# MCU_Board.net
KiCad netlist of a schematic drawn in Altium Designer
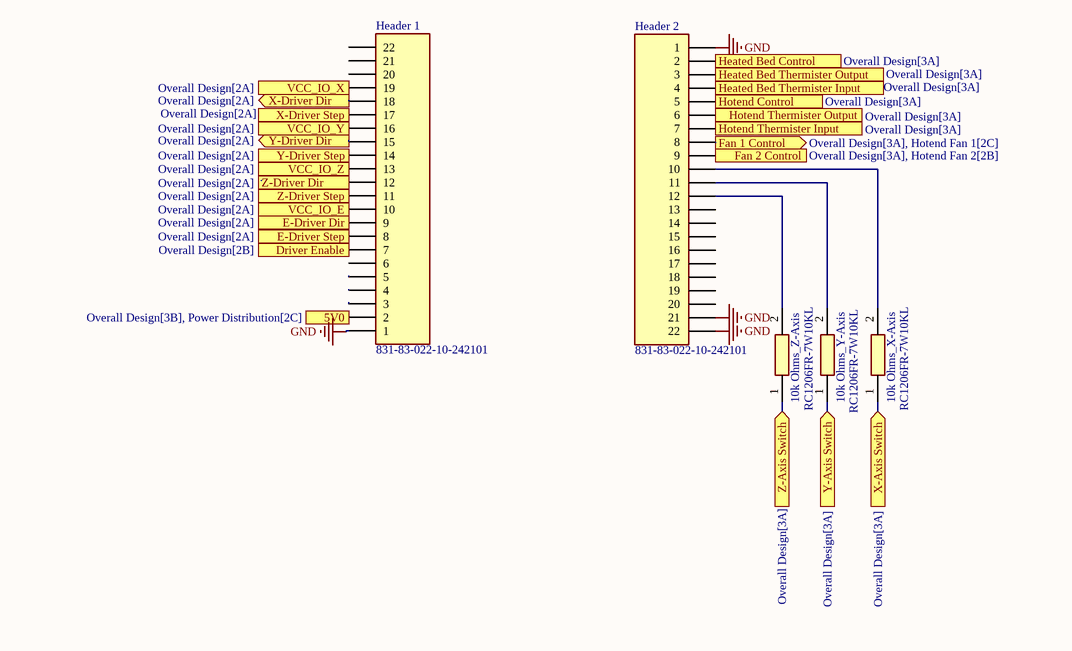
[diagram p0: MCU Board.SchDoc]

(export (version "E")
  (design (tool "Eeschema 10.0.6"))
  (components
    (comp (ref "10k Ohms_X-Axis")
      (value "RC1206FR-7W10KL")
      (footprint "SamacSys:RESC3116X65N")
      (description "Resistor")
      (libsource (lib "*") (part "RC1206FR-7W10KL"))
    )
    (comp (ref "10k Ohms_Y-Axis")
      (value "RC1206FR-7W10KL")
      (footprint "SamacSys:RESC3116X65N")
      (description "Resistor")
      (libsource (lib "*") (part "RC1206FR-7W10KL"))
    )
    (comp (ref "10k Ohms_Z-Axis")
      (value "RC1206FR-7W10KL")
      (footprint "SamacSys:RESC3116X65N")
      (description "Resistor")
      (libsource (lib "*") (part "RC1206FR-7W10KL"))
    )
    (comp (ref "Header 1")
      (value "831-83-022-10-242101")
      (footprint "SamacSys:8318302210242101")
      (description "Connector")
      (libsource (lib "") (part "831-83-022-10-242101_1"))
    )
    (comp (ref "Header 2")
      (value "831-83-022-10-242101")
      (footprint "SamacSys:8318302210242101")
      (description "Connector")
      (libsource (lib "*") (part "831-83-022-10-242101"))
    )
  )
  (nets
    (net (code "1") (name "/5V0") (class "Default")
      (node (ref "Header 1") (pin "2") (pinfunction "2_2") (pintype "passive"))
    )
    (net (code "2") (name "/Driver Enable") (class "Default")
      (node (ref "Header 1") (pin "7") (pinfunction "7_7") (pintype "passive"))
    )
    (net (code "4") (name "/E-Driver Dir") (class "Default")
      (node (ref "Header 1") (pin "9") (pinfunction "9_9") (pintype "passive"))
    )
    (net (code "5") (name "/E-Driver Step") (class "Default")
      (node (ref "Header 1") (pin "8") (pinfunction "8_8") (pintype "passive"))
    )
    (net (code "13") (name "/Fan 1 Control") (class "Default")
      (node (ref "Header 2") (pin "8") (pinfunction "8_8") (pintype "passive"))
    )
    (net (code "14") (name "/Fan 2 Control") (class "Default")
      (node (ref "Header 2") (pin "9") (pinfunction "9_9") (pintype "passive"))
    )
    (net (code "15") (name "/Heated Bed Control") (class "Default")
      (node (ref "Header 2") (pin "2") (pinfunction "2_2") (pintype "passive"))
    )
    (net (code "16") (name "/Heated Bed Thermister Input") (class "Default")
      (node (ref "Header 2") (pin "4") (pinfunction "4_4") (pintype "passive"))
    )
    (net (code "17") (name "/Heated Bed Thermister Output") (class "Default")
      (node (ref "Header 2") (pin "3") (pinfunction "3_3") (pintype "passive"))
    )
    (net (code "18") (name "/Hotend Control") (class "Default")
      (node (ref "Header 2") (pin "5") (pinfunction "5_5") (pintype "passive"))
    )
    (net (code "19") (name "/Hotend Thermister Input") (class "Default")
      (node (ref "Header 2") (pin "7") (pinfunction "7_7") (pintype "passive"))
    )
    (net (code "20") (name "/Hotend Thermister Output") (class "Default")
      (node (ref "Header 2") (pin "6") (pinfunction "6_6") (pintype "passive"))
    )
    (net (code "21") (name "/VCC_IO_E") (class "Default")
      (node (ref "Header 1") (pin "10") (pinfunction "10_10") (pintype "passive"))
    )
    (net (code "22") (name "/VCC_IO_X") (class "Default")
      (node (ref "Header 1") (pin "19") (pinfunction "19_19") (pintype "passive"))
    )
    (net (code "23") (name "/VCC_IO_Y") (class "Default")
      (node (ref "Header 1") (pin "16") (pinfunction "16_16") (pintype "passive"))
    )
    (net (code "24") (name "/VCC_IO_Z") (class "Default")
      (node (ref "Header 1") (pin "13") (pinfunction "13_13") (pintype "passive"))
    )
    (net (code "25") (name "/X-Axis Switch") (class "Default")
      (node (ref "10k Ohms_X-Axis") (pin "1") (pinfunction "1_1") (pintype "passive"))
    )
    (net (code "26") (name "/X-Driver Dir") (class "Default")
      (node (ref "Header 1") (pin "18") (pinfunction "18_18") (pintype "passive"))
    )
    (net (code "27") (name "/X-Driver Step") (class "Default")
      (node (ref "Header 1") (pin "17") (pinfunction "17_17") (pintype "passive"))
    )
    (net (code "28") (name "/Y-Axis Switch") (class "Default")
      (node (ref "10k Ohms_Y-Axis") (pin "1") (pinfunction "1_1") (pintype "passive"))
    )
    (net (code "29") (name "/Y-Driver Dir") (class "Default")
      (node (ref "Header 1") (pin "15") (pinfunction "15_15") (pintype "passive"))
    )
    (net (code "30") (name "/Y-Driver Step") (class "Default")
      (node (ref "Header 1") (pin "14") (pinfunction "14_14") (pintype "passive"))
    )
    (net (code "31") (name "/Z-Axis Switch") (class "Default")
      (node (ref "10k Ohms_Z-Axis") (pin "1") (pinfunction "1_1") (pintype "passive"))
    )
    (net (code "32") (name "/Z-Driver Dir") (class "Default")
      (node (ref "Header 1") (pin "12") (pinfunction "12_12") (pintype "passive"))
    )
    (net (code "33") (name "/Z-Driver Step") (class "Default")
      (node (ref "Header 1") (pin "11") (pinfunction "11_11") (pintype "passive"))
    )
    (net (code "34") (name "GND") (class "Default")
      (node (ref "Header 1") (pin "1") (pinfunction "1_1") (pintype "passive"))
      (node (ref "Header 2") (pin "1") (pinfunction "1_1") (pintype "passive"))
      (node (ref "Header 2") (pin "21") (pinfunction "21_21") (pintype "passive"))
      (node (ref "Header 2") (pin "22") (pinfunction "22_22") (pintype "passive"))
    )
    (net (code "35") (name "Net-(10k Ohms_X-Axis-Pad2)") (class "Default")
      (node (ref "10k Ohms_X-Axis") (pin "2") (pinfunction "2_2") (pintype "passive"))
      (node (ref "Header 2") (pin "10") (pinfunction "10_10") (pintype "passive"))
    )
    (net (code "36") (name "Net-(10k Ohms_Y-Axis-Pad2)") (class "Default")
      (node (ref "10k Ohms_Y-Axis") (pin "2") (pinfunction "2_2") (pintype "passive"))
      (node (ref "Header 2") (pin "11") (pinfunction "11_11") (pintype "passive"))
    )
    (net (code "37") (name "Net-(10k Ohms_Z-Axis-Pad2)") (class "Default")
      (node (ref "10k Ohms_Z-Axis") (pin "2") (pinfunction "2_2") (pintype "passive"))
      (node (ref "Header 2") (pin "12") (pinfunction "12_12") (pintype "passive"))
    )
    (net (code "38") (name "unconnected-(Header 1-Pad3)") (class "Default")
      (node (ref "Header 1") (pin "3") (pinfunction "3_3") (pintype "passive"))
    )
    (net (code "39") (name "unconnected-(Header 1-Pad4)") (class "Default")
      (node (ref "Header 1") (pin "4") (pinfunction "4_4") (pintype "passive"))
    )
    (net (code "40") (name "unconnected-(Header 1-Pad5)") (class "Default")
      (node (ref "Header 1") (pin "5") (pinfunction "5_5") (pintype "passive"))
    )
    (net (code "41") (name "unconnected-(Header 1-Pad6)") (class "Default")
      (node (ref "Header 1") (pin "6") (pinfunction "6_6") (pintype "passive"))
    )
    (net (code "42") (name "unconnected-(Header 1-Pad20)") (class "Default")
      (node (ref "Header 1") (pin "20") (pinfunction "20_20") (pintype "passive"))
    )
    (net (code "43") (name "unconnected-(Header 1-Pad21)") (class "Default")
      (node (ref "Header 1") (pin "21") (pinfunction "21_21") (pintype "passive"))
    )
    (net (code "44") (name "unconnected-(Header 1-Pad22)") (class "Default")
      (node (ref "Header 1") (pin "22") (pinfunction "22_22") (pintype "passive"))
    )
    (net (code "45") (name "unconnected-(Header 2-Pad13)") (class "Default")
      (node (ref "Header 2") (pin "13") (pinfunction "13_13") (pintype "passive"))
    )
    (net (code "46") (name "unconnected-(Header 2-Pad14)") (class "Default")
      (node (ref "Header 2") (pin "14") (pinfunction "14_14") (pintype "passive"))
    )
    (net (code "47") (name "unconnected-(Header 2-Pad15)") (class "Default")
      (node (ref "Header 2") (pin "15") (pinfunction "15_15") (pintype "passive"))
    )
    (net (code "48") (name "unconnected-(Header 2-Pad16)") (class "Default")
      (node (ref "Header 2") (pin "16") (pinfunction "16_16") (pintype "passive"))
    )
    (net (code "49") (name "unconnected-(Header 2-Pad17)") (class "Default")
      (node (ref "Header 2") (pin "17") (pinfunction "17_17") (pintype "passive"))
    )
    (net (code "50") (name "unconnected-(Header 2-Pad18)") (class "Default")
      (node (ref "Header 2") (pin "18") (pinfunction "18_18") (pintype "passive"))
    )
    (net (code "51") (name "unconnected-(Header 2-Pad19)") (class "Default")
      (node (ref "Header 2") (pin "19") (pinfunction "19_19") (pintype "passive"))
    )
    (net (code "52") (name "unconnected-(Header 2-Pad20)") (class "Default")
      (node (ref "Header 2") (pin "20") (pinfunction "20_20") (pintype "passive"))
    )
  )
)
